# Breadboard.net
KiCad netlist of a schematic drawn in EAGLE
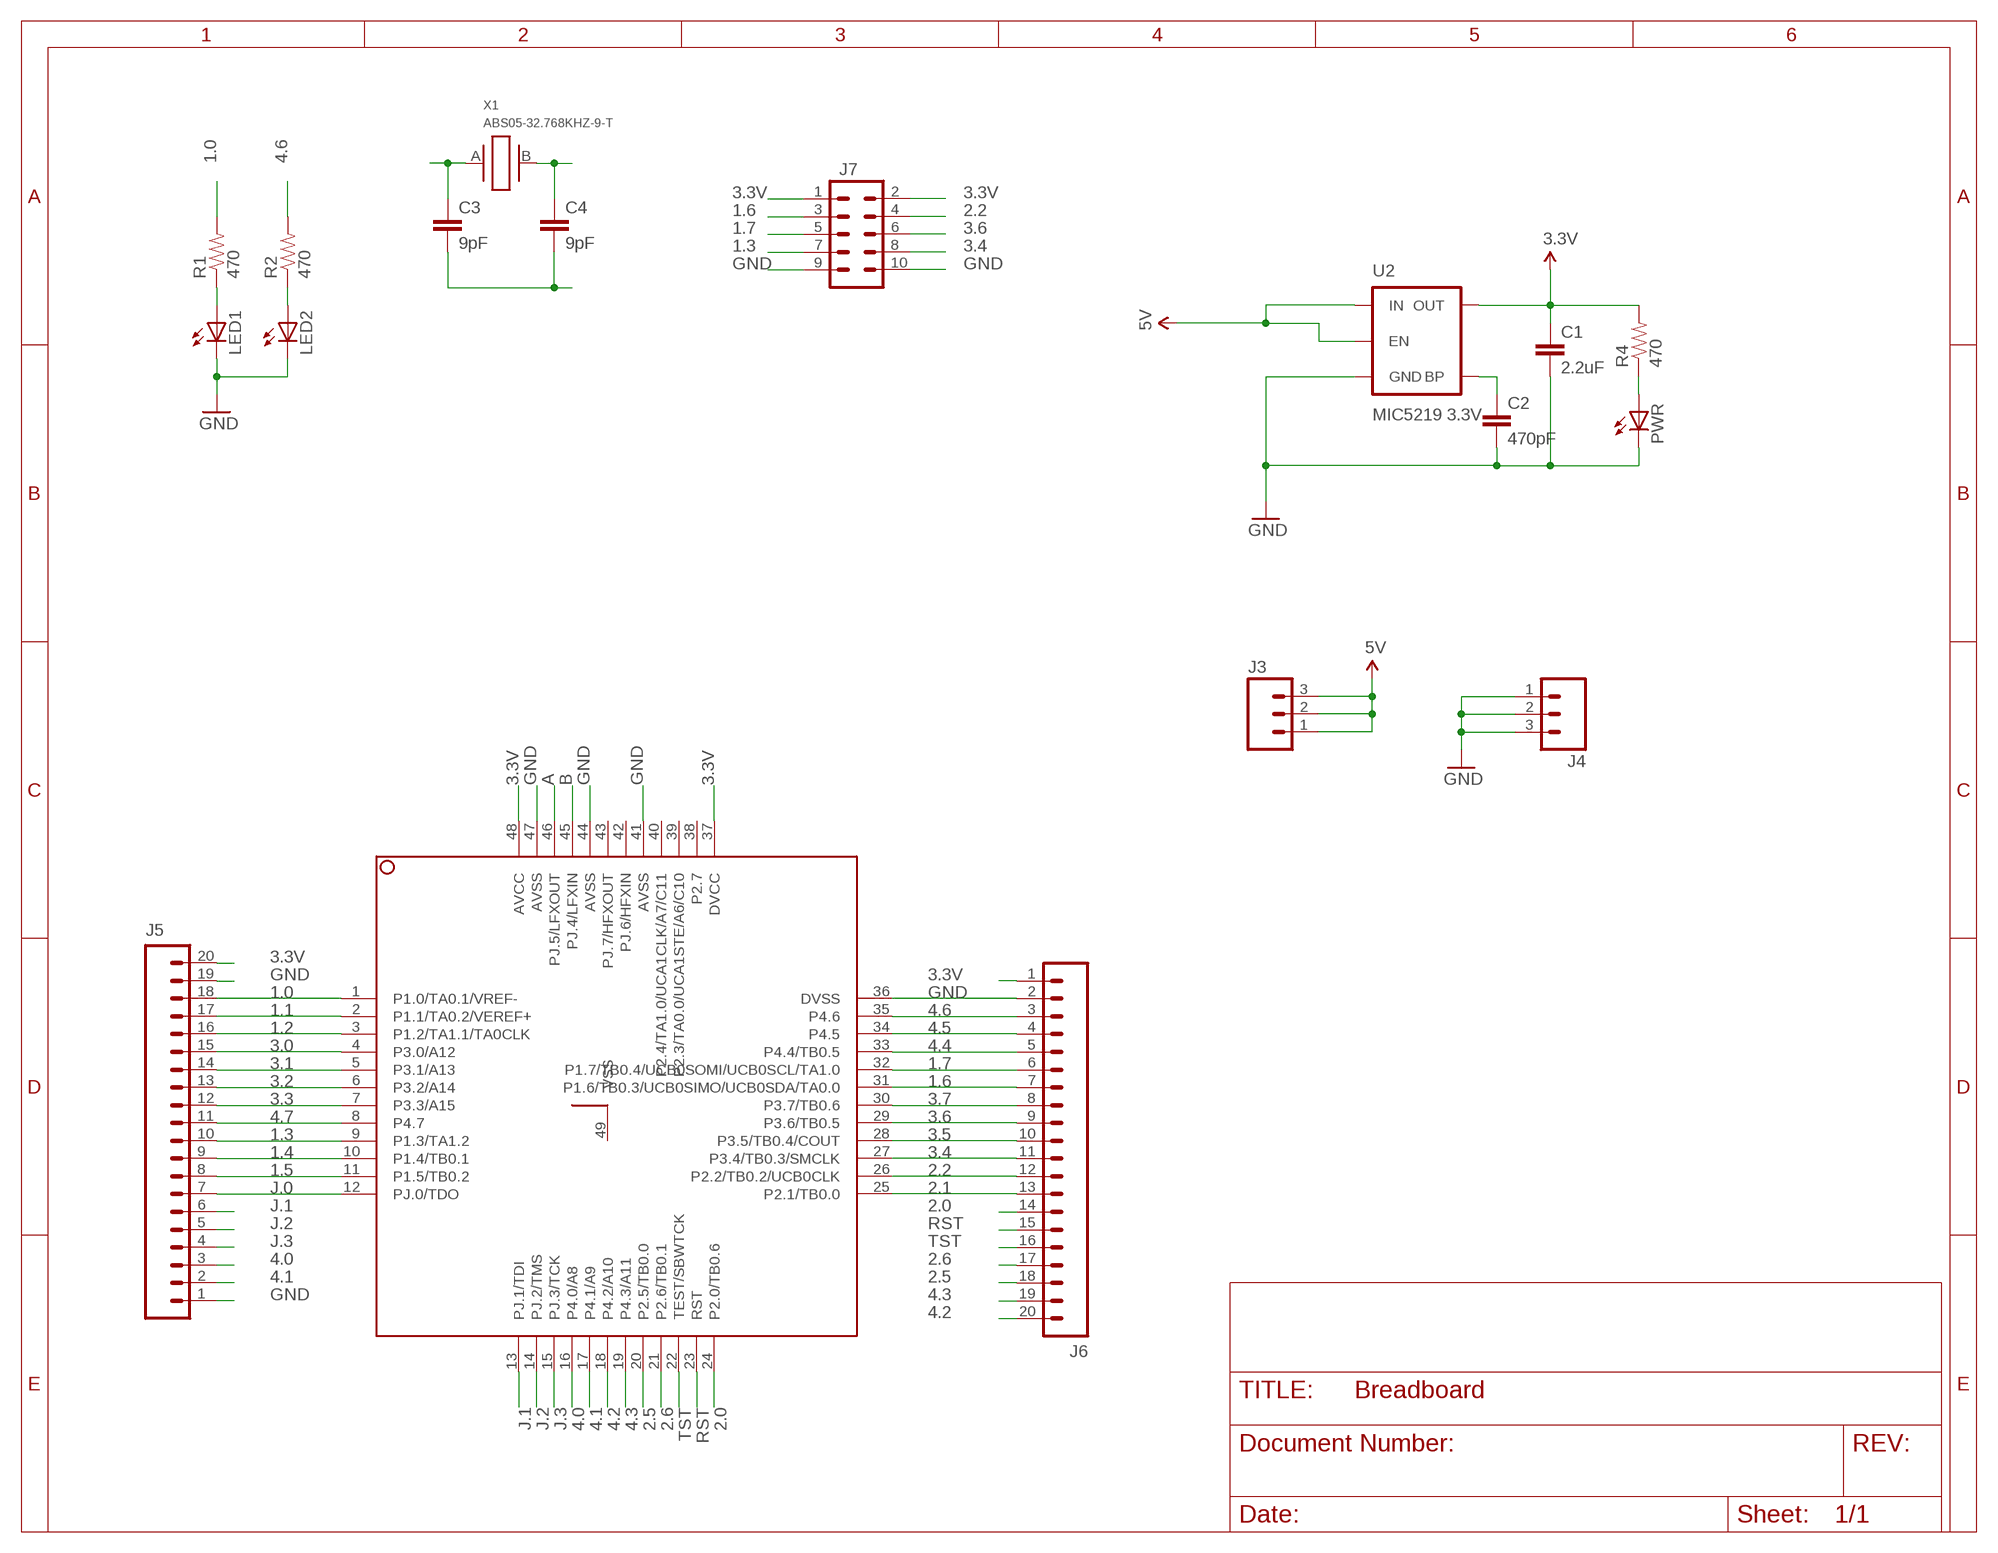
[diagram p0: schematic, sheet 1]

(export (version "E")
  (design (tool "Eeschema 10.0.6"))
  (components
    (comp (ref "C1")
      (value "2.2uF")
      (footprint "eagle-import:0603-CAP")
      (libsource (lib "eagle-import") (part "2.2UF-10V-20%(0603)"))
    )
    (comp (ref "C2")
      (value "470pF")
      (footprint "eagle-import:0603-CAP")
      (libsource (lib "eagle-import") (part "470PF-50V-5%(0603)SMD"))
    )
    (comp (ref "C3")
      (value "9pF")
      (footprint "eagle-import:0603-CAP")
      (libsource (lib "eagle-import") (part "9.0PF-50V-10%(0603)"))
    )
    (comp (ref "C4")
      (value "9pF")
      (footprint "eagle-import:0603-CAP")
      (libsource (lib "eagle-import") (part "9.0PF-50V-10%(0603)"))
    )
    (comp (ref "J3")
      (value "M031X03_NO_SILK")
      (footprint "eagle-import:1X03_NO_SILK")
      (libsource (lib "eagle-import") (part "M031X03_NO_SILK"))
    )
    (comp (ref "J4")
      (value "M031X03_NO_SILK")
      (footprint "eagle-import:1X03_NO_SILK")
      (libsource (lib "eagle-import") (part "M031X03_NO_SILK"))
    )
    (comp (ref "J5")
      (value "M20NOSILK")
      (footprint "eagle-import:1X20_NOSILK")
      (libsource (lib "eagle-import") (part "M20NOSILK"))
    )
    (comp (ref "J6")
      (value "M20NOSILK")
      (footprint "eagle-import:1X20_NOSILK")
      (libsource (lib "eagle-import") (part "M20NOSILK"))
    )
    (comp (ref "J7")
      (value "M05X2NO_SILK")
      (footprint "eagle-import:2X5_NOSILK")
      (libsource (lib "eagle-import") (part "M05X2NO_SILK"))
    )
    (comp (ref "LED1")
      (value "LEDCHIPLED_0805")
      (footprint "eagle-import:CHIPLED_0805")
      (libsource (lib "eagle-import") (part "LEDCHIPLED_0805"))
    )
    (comp (ref "LED2")
      (value "LEDCHIPLED_0805")
      (footprint "eagle-import:CHIPLED_0805")
      (libsource (lib "eagle-import") (part "LEDCHIPLED_0805"))
    )
    (comp (ref "PWR")
      (value "LEDCHIPLED_0805")
      (footprint "eagle-import:CHIPLED_0805")
      (libsource (lib "eagle-import") (part "LEDCHIPLED_0805"))
    )
    (comp (ref "R1")
      (value "470")
      (footprint "eagle-import:0805")
      (libsource (lib "eagle-import") (part "RESISTOR0805-RES"))
    )
    (comp (ref "R2")
      (value "470")
      (footprint "eagle-import:0805")
      (libsource (lib "eagle-import") (part "RESISTOR0805-RES"))
    )
    (comp (ref "R4")
      (value "470")
      (footprint "eagle-import:0805")
      (libsource (lib "eagle-import") (part "RESISTOR0805-RES"))
    )
    (comp (ref "U1")
      (value "MSP430FR5969_RGZ_48")
      (footprint "eagle-import:RGZ48_4P1X4P1")
      (fields (field (name "MANUFACTURER_PART_NUMBER") "msp430fr5969_rgz_48"))
      (libsource (lib "eagle-import") (part "MSP430FR5969_RGZ_48"))
    )
    (comp (ref "U2")
      (value "MIC5219 3.3V")
      (footprint "eagle-import:SOT23-5")
      (libsource (lib "eagle-import") (part "V_REG_MIC52193.3V"))
    )
    (comp (ref "X1")
      (value "ABS05-32.768KHZ-9-T")
      (footprint "eagle-import:ABS05")
      (libsource (lib "eagle-import") (part "ABS05-32.768KHZ-9-T"))
    )
  )
  (nets
    (net (code "1") (name "/1.0") (class "Default")
      (node (ref "J5") (pin "18") (pinfunction "18_18") (pintype "passive"))
      (node (ref "R1") (pin "2") (pinfunction "2_2") (pintype "passive"))
      (node (ref "U1") (pin "1") (pinfunction "P1.0/TA0.1/VREF-_1") (pintype "bidirectional"))
    )
    (net (code "2") (name "/1.1") (class "Default")
      (node (ref "J5") (pin "17") (pinfunction "17_17") (pintype "passive"))
      (node (ref "U1") (pin "2") (pinfunction "P1.1/TA0.2/VEREF+_2") (pintype "bidirectional"))
    )
    (net (code "3") (name "/1.2") (class "Default")
      (node (ref "J5") (pin "16") (pinfunction "16_16") (pintype "passive"))
      (node (ref "U1") (pin "3") (pinfunction "P1.2/TA1.1/TA0CLK_3") (pintype "bidirectional"))
    )
    (net (code "4") (name "/1.3") (class "Default")
      (node (ref "J5") (pin "10") (pinfunction "10_10") (pintype "passive"))
      (node (ref "J7") (pin "7") (pinfunction "7_7") (pintype "passive"))
      (node (ref "U1") (pin "9") (pinfunction "P1.3/TA1.2_9") (pintype "bidirectional"))
    )
    (net (code "5") (name "/1.4") (class "Default")
      (node (ref "J5") (pin "9") (pinfunction "9_9") (pintype "passive"))
      (node (ref "U1") (pin "10") (pinfunction "P1.4/TB0.1_10") (pintype "bidirectional"))
    )
    (net (code "6") (name "/1.5") (class "Default")
      (node (ref "J5") (pin "8") (pinfunction "8_8") (pintype "passive"))
      (node (ref "U1") (pin "11") (pinfunction "P1.5/TB0.2_11") (pintype "bidirectional"))
    )
    (net (code "7") (name "/1.6") (class "Default")
      (node (ref "J6") (pin "7") (pinfunction "7_7") (pintype "passive"))
      (node (ref "J7") (pin "3") (pinfunction "3_3") (pintype "passive"))
      (node (ref "U1") (pin "31") (pinfunction "P1.6/TB0.3/UCB0SIMO/UCB0SDA/TA0.0_31") (pintype "bidirectional"))
    )
    (net (code "8") (name "/1.7") (class "Default")
      (node (ref "J6") (pin "6") (pinfunction "6_6") (pintype "passive"))
      (node (ref "J7") (pin "5") (pinfunction "5_5") (pintype "passive"))
      (node (ref "U1") (pin "32") (pinfunction "P1.7/TB0.4/UCB0SOMI/UCB0SCL/TA1.0_32") (pintype "bidirectional"))
    )
    (net (code "9") (name "/2.0") (class "Default")
      (node (ref "J6") (pin "14") (pinfunction "14_14") (pintype "passive"))
      (node (ref "U1") (pin "24") (pinfunction "P2.0/TB0.6_24") (pintype "bidirectional"))
    )
    (net (code "10") (name "/2.1") (class "Default")
      (node (ref "J6") (pin "13") (pinfunction "13_13") (pintype "passive"))
      (node (ref "U1") (pin "25") (pinfunction "P2.1/TB0.0_25") (pintype "bidirectional"))
    )
    (net (code "11") (name "/2.2") (class "Default")
      (node (ref "J6") (pin "12") (pinfunction "12_12") (pintype "passive"))
      (node (ref "J7") (pin "4") (pinfunction "4_4") (pintype "passive"))
      (node (ref "U1") (pin "26") (pinfunction "P2.2/TB0.2/UCB0CLK_26") (pintype "bidirectional"))
    )
    (net (code "12") (name "/2.5") (class "Default")
      (node (ref "J6") (pin "18") (pinfunction "18_18") (pintype "passive"))
      (node (ref "U1") (pin "20") (pinfunction "P2.5/TB0.0_20") (pintype "bidirectional"))
    )
    (net (code "13") (name "/2.6") (class "Default")
      (node (ref "J6") (pin "17") (pinfunction "17_17") (pintype "passive"))
      (node (ref "U1") (pin "21") (pinfunction "P2.6/TB0.1_21") (pintype "bidirectional"))
    )
    (net (code "14") (name "/3.0") (class "Default")
      (node (ref "J5") (pin "15") (pinfunction "15_15") (pintype "passive"))
      (node (ref "U1") (pin "4") (pinfunction "P3.0/A12_4") (pintype "bidirectional"))
    )
    (net (code "15") (name "/3.1") (class "Default")
      (node (ref "J5") (pin "14") (pinfunction "14_14") (pintype "passive"))
      (node (ref "U1") (pin "5") (pinfunction "P3.1/A13_5") (pintype "bidirectional"))
    )
    (net (code "16") (name "/3.2") (class "Default")
      (node (ref "J5") (pin "13") (pinfunction "13_13") (pintype "passive"))
      (node (ref "U1") (pin "6") (pinfunction "P3.2/A14_6") (pintype "bidirectional"))
    )
    (net (code "17") (name "/3.3") (class "Default")
      (node (ref "J5") (pin "12") (pinfunction "12_12") (pintype "passive"))
      (node (ref "U1") (pin "7") (pinfunction "P3.3/A15_7") (pintype "bidirectional"))
    )
    (net (code "18") (name "/3.4") (class "Default")
      (node (ref "J6") (pin "11") (pinfunction "11_11") (pintype "passive"))
      (node (ref "J7") (pin "8") (pinfunction "8_8") (pintype "passive"))
      (node (ref "U1") (pin "27") (pinfunction "P3.4/TB0.3/SMCLK_27") (pintype "bidirectional"))
    )
    (net (code "19") (name "/3.5") (class "Default")
      (node (ref "J6") (pin "10") (pinfunction "10_10") (pintype "passive"))
      (node (ref "U1") (pin "28") (pinfunction "P3.5/TB0.4/COUT_28") (pintype "bidirectional"))
    )
    (net (code "20") (name "/3.6") (class "Default")
      (node (ref "J6") (pin "9") (pinfunction "9_9") (pintype "passive"))
      (node (ref "J7") (pin "6") (pinfunction "6_6") (pintype "passive"))
      (node (ref "U1") (pin "29") (pinfunction "P3.6/TB0.5_29") (pintype "bidirectional"))
    )
    (net (code "21") (name "/3.7") (class "Default")
      (node (ref "J6") (pin "8") (pinfunction "8_8") (pintype "passive"))
      (node (ref "U1") (pin "30") (pinfunction "P3.7/TB0.6_30") (pintype "bidirectional"))
    )
    (net (code "22") (name "/4.0") (class "Default")
      (node (ref "J5") (pin "3") (pinfunction "3_3") (pintype "passive"))
      (node (ref "U1") (pin "16") (pinfunction "P4.0/A8_16") (pintype "bidirectional"))
    )
    (net (code "23") (name "/4.1") (class "Default")
      (node (ref "J5") (pin "2") (pinfunction "2_2") (pintype "passive"))
      (node (ref "U1") (pin "17") (pinfunction "P4.1/A9_17") (pintype "bidirectional"))
    )
    (net (code "24") (name "/4.2") (class "Default")
      (node (ref "J6") (pin "20") (pinfunction "20_20") (pintype "passive"))
      (node (ref "U1") (pin "18") (pinfunction "P4.2/A10_18") (pintype "bidirectional"))
    )
    (net (code "25") (name "/4.3") (class "Default")
      (node (ref "J6") (pin "19") (pinfunction "19_19") (pintype "passive"))
      (node (ref "U1") (pin "19") (pinfunction "P4.3/A11_19") (pintype "bidirectional"))
    )
    (net (code "26") (name "/4.4") (class "Default")
      (node (ref "J6") (pin "5") (pinfunction "5_5") (pintype "passive"))
      (node (ref "U1") (pin "33") (pinfunction "P4.4/TB0.5_33") (pintype "bidirectional"))
    )
    (net (code "27") (name "/4.5") (class "Default")
      (node (ref "J6") (pin "4") (pinfunction "4_4") (pintype "passive"))
      (node (ref "U1") (pin "34") (pinfunction "P4.5_34") (pintype "bidirectional"))
    )
    (net (code "28") (name "/4.6") (class "Default")
      (node (ref "J6") (pin "3") (pinfunction "3_3") (pintype "passive"))
      (node (ref "R2") (pin "2") (pinfunction "2_2") (pintype "passive"))
      (node (ref "U1") (pin "35") (pinfunction "P4.6_35") (pintype "bidirectional"))
    )
    (net (code "29") (name "/4.7") (class "Default")
      (node (ref "J5") (pin "11") (pinfunction "11_11") (pintype "passive"))
      (node (ref "U1") (pin "8") (pinfunction "P4.7_8") (pintype "bidirectional"))
    )
    (net (code "30") (name "/A") (class "Default")
      (node (ref "C3") (pin "1") (pinfunction "1_1") (pintype "passive"))
      (node (ref "U1") (pin "46") (pinfunction "PJ.5/LFXOUT_46") (pintype "bidirectional"))
      (node (ref "X1") (pin "A") (pinfunction "1_A") (pintype "bidirectional"))
    )
    (net (code "31") (name "/B") (class "Default")
      (node (ref "C4") (pin "1") (pinfunction "1_1") (pintype "passive"))
      (node (ref "U1") (pin "45") (pinfunction "PJ.4/LFXIN_45") (pintype "bidirectional"))
      (node (ref "X1") (pin "B") (pinfunction "2_B") (pintype "bidirectional"))
    )
    (net (code "32") (name "/J.0") (class "Default")
      (node (ref "J5") (pin "7") (pinfunction "7_7") (pintype "passive"))
      (node (ref "U1") (pin "12") (pinfunction "PJ.0/TDO_12") (pintype "bidirectional"))
    )
    (net (code "33") (name "/J.1") (class "Default")
      (node (ref "J5") (pin "6") (pinfunction "6_6") (pintype "passive"))
      (node (ref "U1") (pin "13") (pinfunction "PJ.1/TDI_13") (pintype "bidirectional"))
    )
    (net (code "34") (name "/J.2") (class "Default")
      (node (ref "J5") (pin "5") (pinfunction "5_5") (pintype "passive"))
      (node (ref "U1") (pin "14") (pinfunction "PJ.2/TMS_14") (pintype "bidirectional"))
    )
    (net (code "35") (name "/J.3") (class "Default")
      (node (ref "J5") (pin "4") (pinfunction "4_4") (pintype "passive"))
      (node (ref "U1") (pin "15") (pinfunction "PJ.3/TCK_15") (pintype "bidirectional"))
    )
    (net (code "36") (name "/RST") (class "Default")
      (node (ref "J6") (pin "15") (pinfunction "15_15") (pintype "passive"))
      (node (ref "U1") (pin "23") (pinfunction "RST_23") (pintype "bidirectional"))
    )
    (net (code "37") (name "/TST") (class "Default")
      (node (ref "J6") (pin "16") (pinfunction "16_16") (pintype "passive"))
      (node (ref "U1") (pin "22") (pinfunction "TEST/SBWTCK_22") (pintype "bidirectional"))
    )
    (net (code "38") (name "3.3V") (class "Default")
      (node (ref "C1") (pin "1") (pinfunction "1_1") (pintype "passive"))
      (node (ref "J5") (pin "20") (pinfunction "20_20") (pintype "passive"))
      (node (ref "J6") (pin "1") (pinfunction "1_1") (pintype "passive"))
      (node (ref "J7") (pin "1") (pinfunction "1_1") (pintype "passive"))
      (node (ref "J7") (pin "2") (pinfunction "2_2") (pintype "passive"))
      (node (ref "R4") (pin "2") (pinfunction "2_2") (pintype "passive"))
      (node (ref "U1") (pin "37") (pinfunction "DVCC_37") (pintype "bidirectional"))
      (node (ref "U1") (pin "48") (pinfunction "AVCC_48") (pintype "bidirectional"))
      (node (ref "U2") (pin "5") (pinfunction "OUT_5") (pintype "passive"))
    )
    (net (code "39") (name "5V") (class "Default")
      (node (ref "J3") (pin "1") (pinfunction "1_1") (pintype "passive"))
      (node (ref "J3") (pin "2") (pinfunction "2_2") (pintype "passive"))
      (node (ref "J3") (pin "3") (pinfunction "3_3") (pintype "passive"))
      (node (ref "U2") (pin "1") (pinfunction "IN_1") (pintype "input"))
      (node (ref "U2") (pin "3") (pinfunction "EN_3") (pintype "input"))
    )
    (net (code "40") (name "GND") (class "Default")
      (node (ref "C1") (pin "2") (pinfunction "2_2") (pintype "passive"))
      (node (ref "C2") (pin "2") (pinfunction "2_2") (pintype "passive"))
      (node (ref "C3") (pin "2") (pinfunction "2_2") (pintype "passive"))
      (node (ref "C4") (pin "2") (pinfunction "2_2") (pintype "passive"))
      (node (ref "J4") (pin "1") (pinfunction "1_1") (pintype "passive"))
      (node (ref "J4") (pin "2") (pinfunction "2_2") (pintype "passive"))
      (node (ref "J4") (pin "3") (pinfunction "3_3") (pintype "passive"))
      (node (ref "J5") (pin "1") (pinfunction "1_1") (pintype "passive"))
      (node (ref "J5") (pin "19") (pinfunction "19_19") (pintype "passive"))
      (node (ref "J6") (pin "2") (pinfunction "2_2") (pintype "passive"))
      (node (ref "J7") (pin "10") (pinfunction "10_10") (pintype "passive"))
      (node (ref "J7") (pin "9") (pinfunction "9_9") (pintype "passive"))
      (node (ref "LED1") (pin "C") (pinfunction "C_C") (pintype "passive"))
      (node (ref "LED2") (pin "C") (pinfunction "C_C") (pintype "passive"))
      (node (ref "PWR") (pin "C") (pinfunction "C_C") (pintype "passive"))
      (node (ref "U1") (pin "36") (pinfunction "DVSS_36") (pintype "bidirectional"))
      (node (ref "U1") (pin "41") (pinfunction "AVSS_41") (pintype "bidirectional"))
      (node (ref "U1") (pin "44") (pinfunction "AVSS_44") (pintype "bidirectional"))
      (node (ref "U1") (pin "47") (pinfunction "AVSS_47") (pintype "bidirectional"))
      (node (ref "U2") (pin "2") (pinfunction "GND_2") (pintype "input"))
    )
    (net (code "41") (name "Net-(LED1-PadA)") (class "Default")
      (node (ref "LED1") (pin "A") (pinfunction "A_A") (pintype "passive"))
      (node (ref "R1") (pin "1") (pinfunction "1_1") (pintype "passive"))
    )
    (net (code "42") (name "Net-(LED2-PadA)") (class "Default")
      (node (ref "LED2") (pin "A") (pinfunction "A_A") (pintype "passive"))
      (node (ref "R2") (pin "1") (pinfunction "1_1") (pintype "passive"))
    )
    (net (code "43") (name "Net-(PWR-PadA)") (class "Default")
      (node (ref "PWR") (pin "A") (pinfunction "A_A") (pintype "passive"))
      (node (ref "R4") (pin "1") (pinfunction "1_1") (pintype "passive"))
    )
    (net (code "44") (name "Net-(U2-BP)") (class "Default")
      (node (ref "C2") (pin "1") (pinfunction "1_1") (pintype "passive"))
      (node (ref "U2") (pin "4") (pinfunction "BP_4") (pintype "input"))
    )
    (net (code "45") (name "unconnected-(U1-P2.3{slash}TA0.0{slash}UCA1STE{slash}A6{slash}C10-Pad39)") (class "Default")
      (node (ref "U1") (pin "39") (pinfunction "P2.3/TA0.0/UCA1STE/A6/C10_39") (pintype "bidirectional"))
    )
    (net (code "46") (name "unconnected-(U1-P2.4{slash}TA1.0{slash}UCA1CLK{slash}A7{slash}C11-Pad40)") (class "Default")
      (node (ref "U1") (pin "40") (pinfunction "P2.4/TA1.0/UCA1CLK/A7/C11_40") (pintype "bidirectional"))
    )
    (net (code "47") (name "unconnected-(U1-P2.7-Pad38)") (class "Default")
      (node (ref "U1") (pin "38") (pinfunction "P2.7_38") (pintype "bidirectional"))
    )
    (net (code "48") (name "unconnected-(U1-PJ.6{slash}HFXIN-Pad42)") (class "Default")
      (node (ref "U1") (pin "42") (pinfunction "PJ.6/HFXIN_42") (pintype "bidirectional"))
    )
    (net (code "49") (name "unconnected-(U1-PJ.7{slash}HFXOUT-Pad43)") (class "Default")
      (node (ref "U1") (pin "43") (pinfunction "PJ.7/HFXOUT_43") (pintype "bidirectional"))
    )
    (net (code "50") (name "unconnected-(U1-VSS-Pad49)") (class "Default")
      (node (ref "U1") (pin "49") (pinfunction "VSS_49") (pintype "bidirectional"))
    )
  )
)
